# Microcontroller.net
KiCad netlist of a schematic drawn in Altium Designer
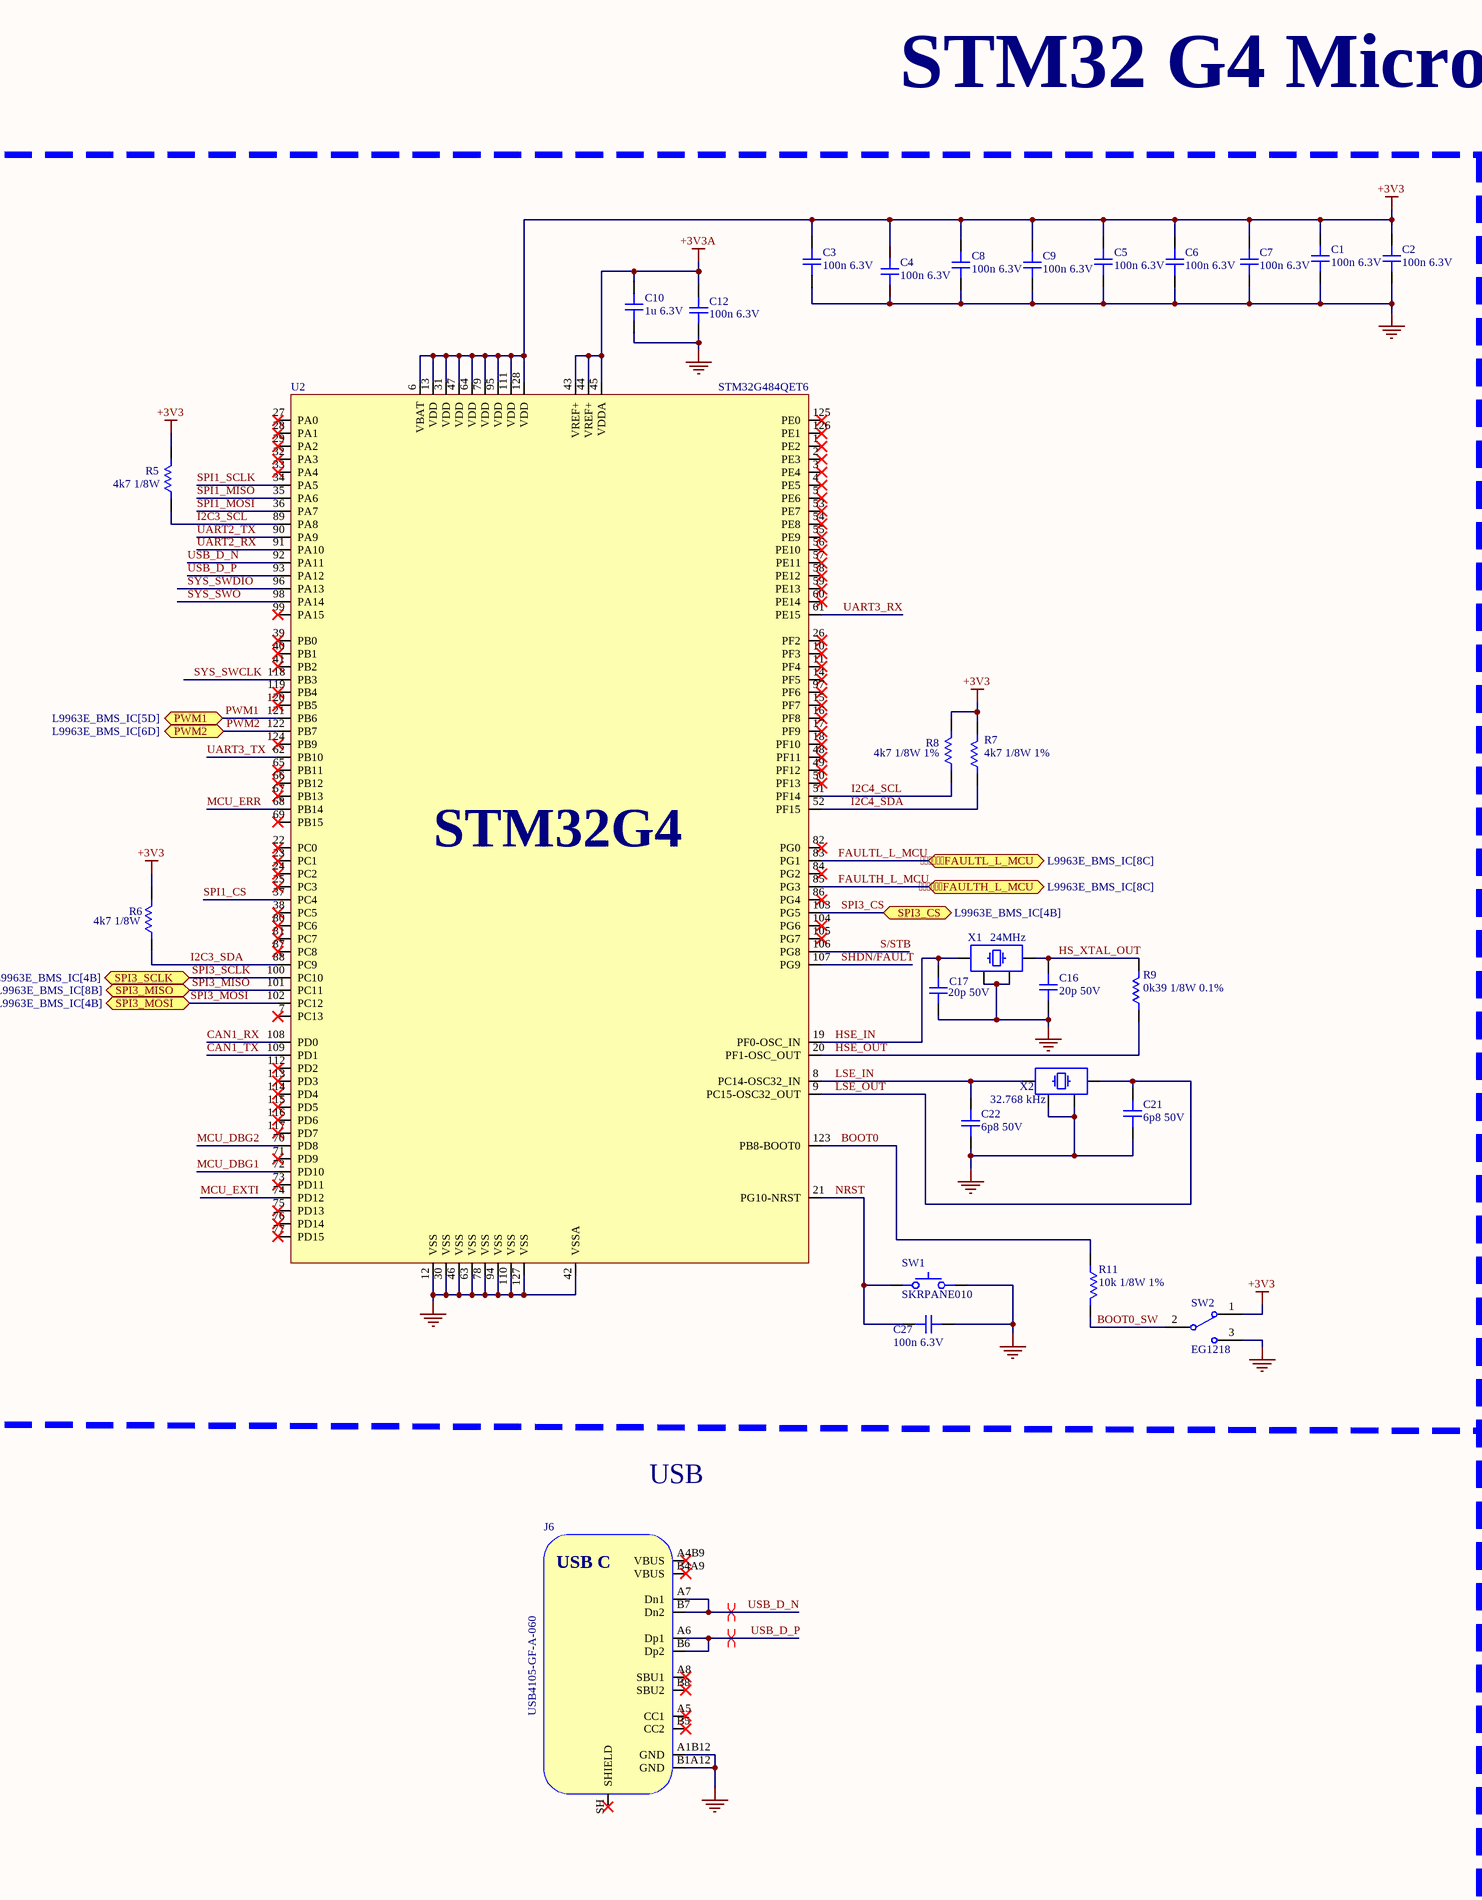
[diagram p0: Microcontroller.SchDoc, left]
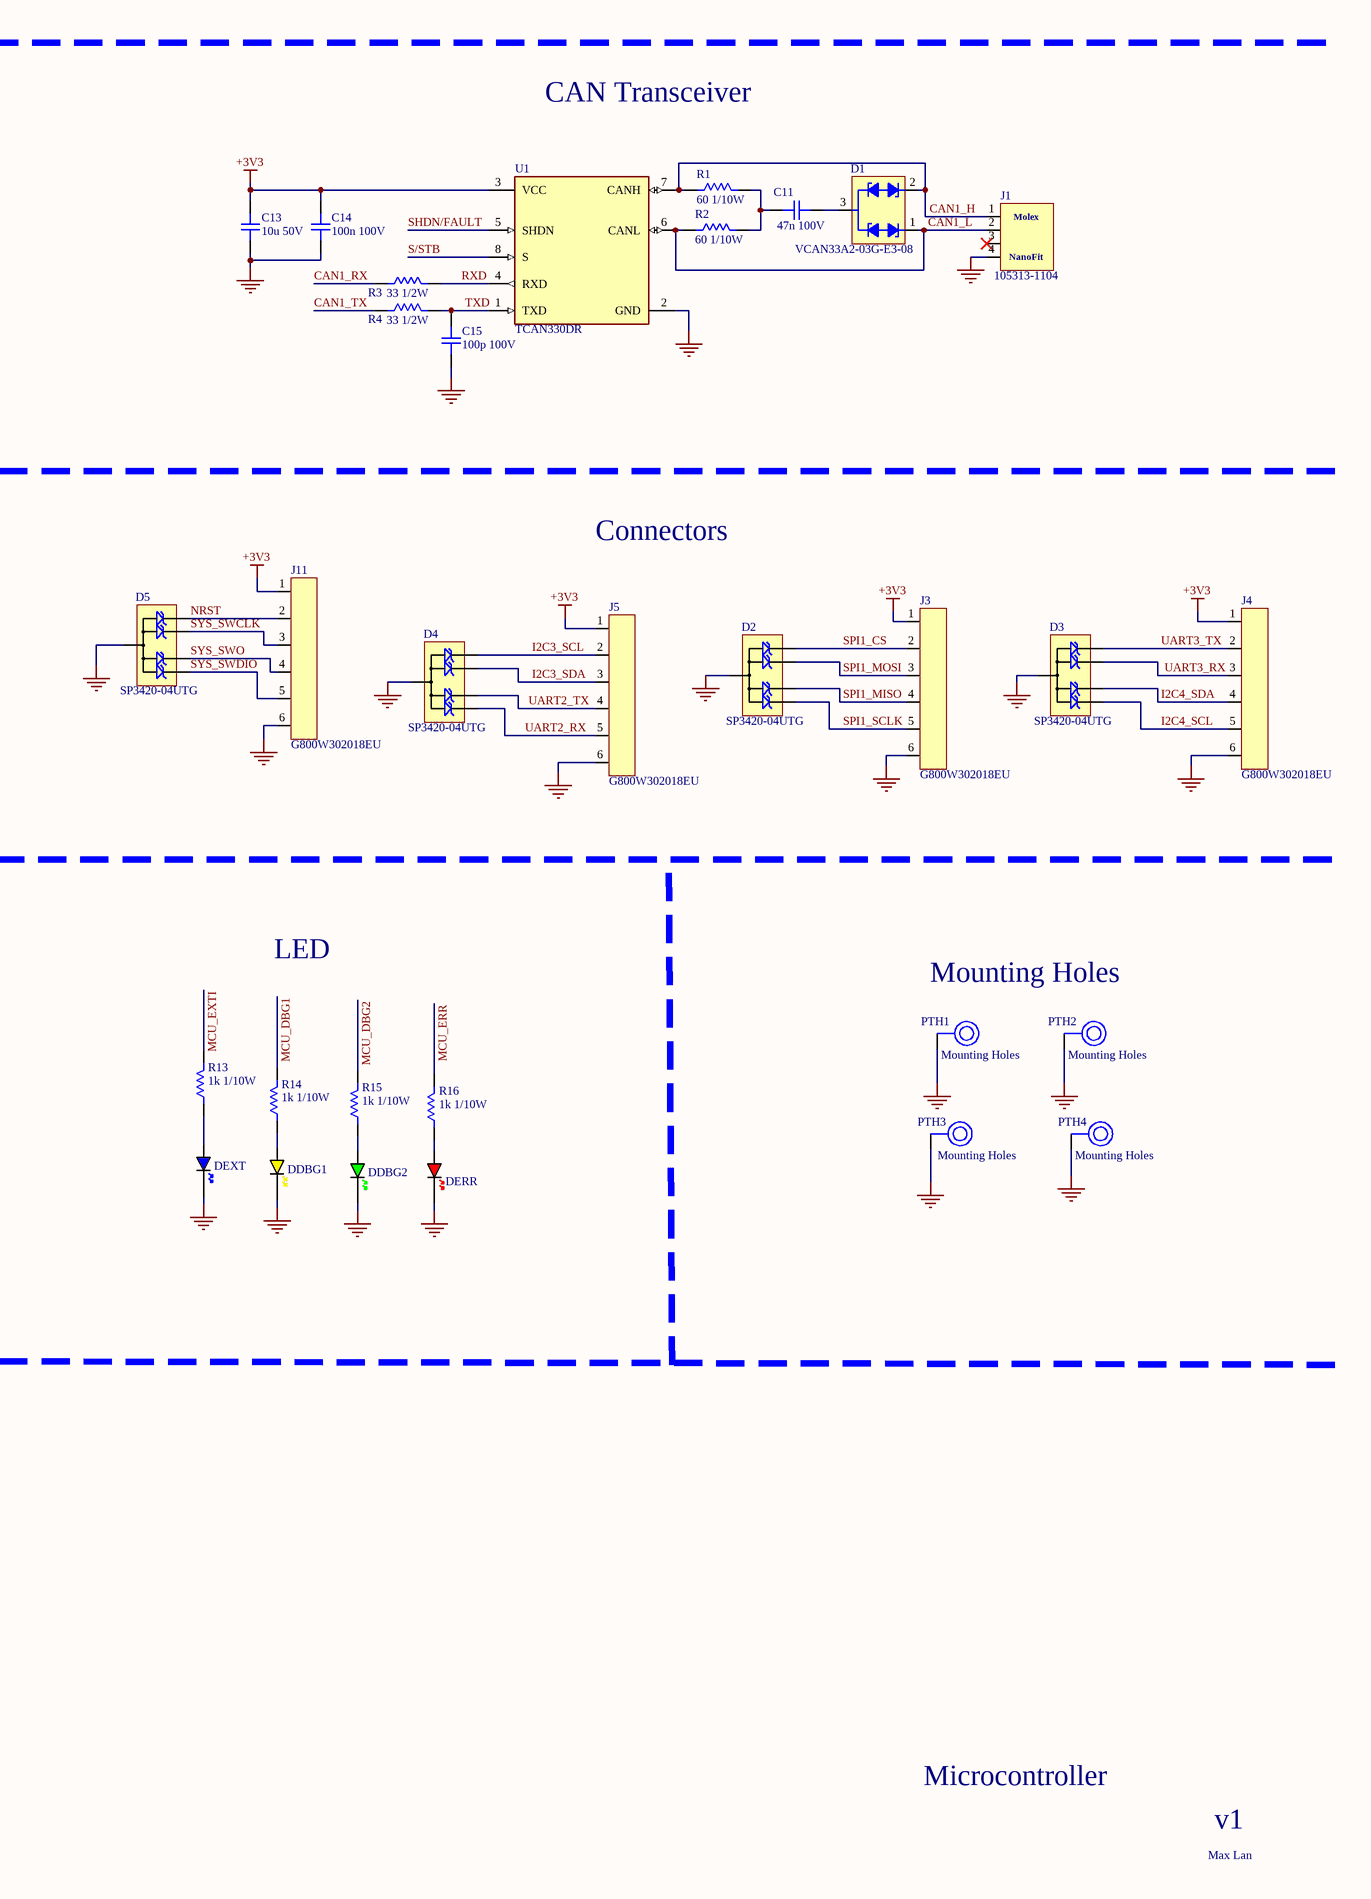
[diagram p1: Microcontroller.SchDoc, right]

(export (version "E")
  (design (tool "Eeschema 10.0.6"))
  (components
    (comp (ref "C1")
      (value "100n 6.3V")
      (footprint "CAP_0603")
      (description "Multilayer Ceramic Capacitors MLCC - SMD/SMT 6.3V .1uF X7R 0603 10%")
      (fields
        (field (name "MANUFACTURER") "KYOCERA AVX")
        (field (name "MANUFACTURER PART NUMBER") "KGM15AR70J104KT")
      )
      (libsource (lib "Schematic-Lib-PhilsLab") (part "KGM15AR70J104KT"))
    )
    (comp (ref "C2")
      (value "100n 6.3V")
      (footprint "CAP_0603")
      (description "Multilayer Ceramic Capacitors MLCC - SMD/SMT 6.3V .1uF X7R 0603 10%")
      (fields
        (field (name "MANUFACTURER") "KYOCERA AVX")
        (field (name "MANUFACTURER PART NUMBER") "KGM15AR70J104KT")
      )
      (libsource (lib "Schematic-Lib-PhilsLab") (part "KGM15AR70J104KT"))
    )
    (comp (ref "C3")
      (value "100n 6.3V")
      (footprint "CAP_0603")
      (description "Multilayer Ceramic Capacitors MLCC - SMD/SMT 6.3V .1uF X7R 0603 10%")
      (fields
        (field (name "MANUFACTURER") "KYOCERA AVX")
        (field (name "MANUFACTURER PART NUMBER") "KGM15AR70J104KT")
      )
      (libsource (lib "Schematic-Lib-PhilsLab") (part "KGM15AR70J104KT"))
    )
    (comp (ref "C4")
      (value "100n 6.3V")
      (footprint "CAP_0603")
      (description "Multilayer Ceramic Capacitors MLCC - SMD/SMT 6.3V .1uF X7R 0603 10%")
      (fields
        (field (name "MANUFACTURER") "KYOCERA AVX")
        (field (name "MANUFACTURER PART NUMBER") "KGM15AR70J104KT")
      )
      (libsource (lib "Schematic-Lib-PhilsLab") (part "KGM15AR70J104KT"))
    )
    (comp (ref "C5")
      (value "100n 6.3V")
      (footprint "CAP_0603")
      (description "Multilayer Ceramic Capacitors MLCC - SMD/SMT 6.3V .1uF X7R 0603 10%")
      (fields
        (field (name "MANUFACTURER") "KYOCERA AVX")
        (field (name "MANUFACTURER PART NUMBER") "KGM15AR70J104KT")
      )
      (libsource (lib "Schematic-Lib-PhilsLab") (part "KGM15AR70J104KT"))
    )
    (comp (ref "C6")
      (value "100n 6.3V")
      (footprint "CAP_0603")
      (description "Multilayer Ceramic Capacitors MLCC - SMD/SMT 6.3V .1uF X7R 0603 10%")
      (fields
        (field (name "MANUFACTURER") "KYOCERA AVX")
        (field (name "MANUFACTURER PART NUMBER") "KGM15AR70J104KT")
      )
      (libsource (lib "Schematic-Lib-PhilsLab") (part "KGM15AR70J104KT"))
    )
    (comp (ref "C7")
      (value "100n 6.3V")
      (footprint "CAP_0603")
      (description "Multilayer Ceramic Capacitors MLCC - SMD/SMT 6.3V .1uF X7R 0603 10%")
      (fields
        (field (name "MANUFACTURER") "KYOCERA AVX")
        (field (name "MANUFACTURER PART NUMBER") "KGM15AR70J104KT")
      )
      (libsource (lib "Schematic-Lib-PhilsLab") (part "KGM15AR70J104KT"))
    )
    (comp (ref "C8")
      (value "100n 6.3V")
      (footprint "CAP_0603")
      (description "Multilayer Ceramic Capacitors MLCC - SMD/SMT 6.3V .1uF X7R 0603 10%")
      (fields
        (field (name "MANUFACTURER") "KYOCERA AVX")
        (field (name "MANUFACTURER PART NUMBER") "KGM15AR70J104KT")
      )
      (libsource (lib "Schematic-Lib-PhilsLab") (part "KGM15AR70J104KT"))
    )
    (comp (ref "C9")
      (value "100n 6.3V")
      (footprint "CAP_0603")
      (description "Multilayer Ceramic Capacitors MLCC - SMD/SMT 6.3V .1uF X7R 0603 10%")
      (fields
        (field (name "MANUFACTURER") "KYOCERA AVX")
        (field (name "MANUFACTURER PART NUMBER") "KGM15AR70J104KT")
      )
      (libsource (lib "Schematic-Lib-PhilsLab") (part "KGM15AR70J104KT"))
    )
    (comp (ref "C10")
      (value "1u 6.3V")
      (footprint "CAP_0603")
      (description "Multilayer Ceramic Capacitors MLCC - SMD/SMT 6.3 Vo 1 uF 0603 X7R 10 % AECQ200")
      (fields
        (field (name "MANUFACTURER") "KEMET")
        (field (name "MANUFACTURER PART NUMBER") "C0603X105K9RACAUTO")
      )
      (libsource (lib "Schematic-Lib-PhilsLab") (part "C0603X105K9RACAUTO"))
    )
    (comp (ref "C11")
      (value "47n 100V")
      (footprint "CAP_0603")
      (description "Multilayer Ceramic Capacitors MLCC - SMD/SMT 100V 0.047uF X7R 0603 5%")
      (fields
        (field (name "MANUFACTURER") "KEMET")
        (field (name "MANUFACTURER PART NUMBER") "C0603C473J1RACTU")
      )
      (libsource (lib "Schematic-Lib-PhilsLab") (part "C0603C473J1RACTU"))
    )
    (comp (ref "C12")
      (value "100n 6.3V")
      (footprint "CAP_0603")
      (description "Multilayer Ceramic Capacitors MLCC - SMD/SMT 6.3V .1uF X7R 0603 10%")
      (fields
        (field (name "MANUFACTURER") "KYOCERA AVX")
        (field (name "MANUFACTURER PART NUMBER") "KGM15AR70J104KT")
      )
      (libsource (lib "Schematic-Lib-PhilsLab") (part "KGM15AR70J104KT"))
    )
    (comp (ref "C13")
      (value "10u 50V")
      (footprint "CAP_1210")
      (description "Multilayer Ceramic Capacitors MLCC - SMD/SMT 50V 10uF X7R 1210 10 % AEC-Q200 FLEXITERM")
      (fields
        (field (name "MANUFACTURER") "KYOCERA AVX")
        (field (name "MANUFACTURER PART NUMBER") "KAF32LR71H106KL")
      )
      (libsource (lib "Schematic-Lib-PhilsLab") (part "KAF32LR71H106KL"))
    )
    (comp (ref "C14")
      (value "100n 100V")
      (footprint "CAP_0603")
      (description "Multilayer Ceramic Capacitors MLCC - SMD/SMT 100V 0.1uF 0603 X7R 10% AECQ2")
      (fields
        (field (name "MANUFACTURER") "TAIYO YUDEN")
        (field (name "MANUFACTURER PART NUMBER") "MAJCH168BB7104KTEA01")
      )
      (libsource (lib "Schematic-Lib-PhilsLab") (part "MAJCH168BB7104KTEA01"))
    )
    (comp (ref "C15")
      (value "100p 100V")
      (footprint "CAP_0603")
      (description "Multilayer Ceramic Capacitors MLCC - SMD/SMT 100V 100pF X7R 0603 5%")
      (fields
        (field (name "MANUFACTURER") "KYOCERA AVX")
        (field (name "MANUFACTURER PART NUMBER") "KGM15AR72A101JT")
      )
      (libsource (lib "Schematic-Lib-PhilsLab") (part "KGM15AR72A101JT"))
    )
    (comp (ref "C16")
      (value "20p 50V")
      (footprint "CAP_0603")
      (description "Multilayer Ceramic Capacitors MLCC - SMD/SMT 50V 20pF 5% X7R 0603")
      (fields (field (name "MANUFACTURER") "KEMET"))
      (libsource (lib "Schematic-Lib-PhilsLab") (part "C0603C200J5RACTU"))
    )
    (comp (ref "C17")
      (value "20p 50V")
      (footprint "CAP_0603")
      (description "Multilayer Ceramic Capacitors MLCC - SMD/SMT 50V 20pF 5% X7R 0603")
      (fields (field (name "MANUFACTURER") "KEMET"))
      (libsource (lib "Schematic-Lib-PhilsLab") (part "C0603C200J5RACTU"))
    )
    (comp (ref "C21")
      (value "6p8 50V")
      (footprint "CAP_0603")
      (description "Multilayer Ceramic Capacitors MLCC - SMD/SMT T101 COMMERCIAL")
      (fields
        (field (name "MANUFACTURER") "KYOCERA AVX")
        (field (name "MANUFACTURER PART NUMBER") "06035C6R8KAT2A")
      )
      (libsource (lib "Schematic-Lib-PhilsLab") (part "06035C6R8KAT2A"))
    )
    (comp (ref "C22")
      (value "6p8 50V")
      (footprint "CAP_0603")
      (description "Multilayer Ceramic Capacitors MLCC - SMD/SMT T101 COMMERCIAL")
      (fields
        (field (name "MANUFACTURER") "KYOCERA AVX")
        (field (name "MANUFACTURER PART NUMBER") "06035C6R8KAT2A")
      )
      (libsource (lib "Schematic-Lib-PhilsLab") (part "06035C6R8KAT2A"))
    )
    (comp (ref "C27")
      (value "100n 6.3V")
      (footprint "CAP_0603")
      (description "Multilayer Ceramic Capacitors MLCC - SMD/SMT 6.3V .1uF X7R 0603 10%")
      (fields
        (field (name "MANUFACTURER") "KYOCERA AVX")
        (field (name "MANUFACTURER PART NUMBER") "KGM15AR70J104KT")
      )
      (libsource (lib "Schematic-Lib-PhilsLab") (part "KGM15AR70J104KT"))
    )
    (comp (ref "D1")
      (value "VCAN33A2-03G-E3-08")
      (footprint "VCAN33A2-03G-E3-08")
      (description "ESD Protection Diodes / TVS Diodes 9.5pF 33V SOT-323")
      (libsource (lib "Schematic-Lib-PhilsLab") (part "VCAN33A2-03G-E3-08"))
    )
    (comp (ref "D2")
      (value "SP3420-04UTG")
      (footprint "uDFN-10")
      (description "TVS Diode Array Low Capacitance ESD Protection 4-Channel (Vwork=3V3, Vclamp=6V)")
      (fields (field (name "MANUFACTURER") "Littelfuse"))
      (libsource (lib "Schematic-Lib-PhilsLab") (part "SP3420-04UTG"))
    )
    (comp (ref "D3")
      (value "SP3420-04UTG")
      (footprint "uDFN-10")
      (description "TVS Diode Array Low Capacitance ESD Protection 4-Channel (Vwork=3V3, Vclamp=6V)")
      (fields (field (name "MANUFACTURER") "Littelfuse"))
      (libsource (lib "Schematic-Lib-PhilsLab") (part "SP3420-04UTG"))
    )
    (comp (ref "D4")
      (value "SP3420-04UTG")
      (footprint "uDFN-10")
      (description "TVS Diode Array Low Capacitance ESD Protection 4-Channel (Vwork=3V3, Vclamp=6V)")
      (fields (field (name "MANUFACTURER") "Littelfuse"))
      (libsource (lib "Schematic-Lib-PhilsLab") (part "SP3420-04UTG"))
    )
    (comp (ref "D5")
      (value "SP3420-04UTG")
      (footprint "uDFN-10")
      (description "TVS Diode Array Low Capacitance ESD Protection 4-Channel (Vwork=3V3, Vclamp=6V)")
      (fields (field (name "MANUFACTURER") "Littelfuse"))
      (libsource (lib "Schematic-Lib-PhilsLab") (part "SP3420-04UTG"))
    )
    (comp (ref "DDBG1")
      (value "YELLOW")
      (footprint "LED_0603_YELLOW")
      (description "LED 0603 YELLOW SMD")
      (libsource (lib "Schematic-Lib-PhilsLab") (part "LED_0603_YELLOW"))
    )
    (comp (ref "DDBG2")
      (value "GREEN")
      (footprint "LED_0603_GREEN")
      (description "LED 0603 GREEN SMD")
      (libsource (lib "Schematic-Lib-PhilsLab") (part "LED_0603_GREEN"))
    )
    (comp (ref "DERR")
      (value "RED")
      (footprint "LED_0603_RED")
      (description "LED 0603 RED SMD")
      (libsource (lib "Schematic-Lib-PhilsLab") (part "LED_0603_RED"))
    )
    (comp (ref "DEXT")
      (value "BLUE")
      (footprint "LED_0603_BLUE")
      (description "LED 0603 BLUE SMD")
      (libsource (lib "Schematic-Lib-PhilsLab") (part "LED_0603_BLUE"))
    )
    (comp (ref "J1")
      (value "105313-1104")
      (footprint "105313-1104")
      (fields (field (name "MANUFACTURER") "Molex"))
      (libsource (lib "Schematic-Lib-PhilsLab") (part "105313-1104"))
    )
    (comp (ref "J3")
      (value "G800W302018EU")
      (footprint "G800W302018EU")
      (description "Pin Header 6 Position 2.54mm Pitch")
      (fields (field (name "MANUFACTURER") "Amphenol"))
      (libsource (lib "Schematic-Lib-PhilsLab") (part "G800W302018EU"))
    )
    (comp (ref "J4")
      (value "G800W302018EU")
      (footprint "G800W302018EU")
      (description "Pin Header 6 Position 2.54mm Pitch")
      (fields (field (name "MANUFACTURER") "Amphenol"))
      (libsource (lib "Schematic-Lib-PhilsLab") (part "G800W302018EU"))
    )
    (comp (ref "J5")
      (value "G800W302018EU")
      (footprint "G800W302018EU")
      (description "Pin Header 6 Position 2.54mm Pitch")
      (fields (field (name "MANUFACTURER") "Amphenol"))
      (libsource (lib "Schematic-Lib-PhilsLab") (part "G800W302018EU"))
    )
    (comp (ref "J6")
      (value "USB4105-GF-A-060")
      (footprint "USB4105-GF-A-060")
      (description "USB Connector Type C SMT 12 Pin")
      (fields (field (name "MANUFACTURER") "GCT"))
      (libsource (lib "Schematic-Lib-PhilsLab") (part "USB4105-GF-A-060"))
    )
    (comp (ref "J11")
      (value "G800W302018EU")
      (footprint "G800W302018EU")
      (description "Pin Header 6 Position 2.54mm Pitch")
      (fields (field (name "MANUFACTURER") "Amphenol"))
      (libsource (lib "Schematic-Lib-PhilsLab") (part "G800W302018EU"))
    )
    (comp (ref "PTH1")
      (value "Mounting Holes")
      (footprint "Mounting Hole")
      (libsource (lib "Schematic-Lib-PhilsLab") (part "Mounting Holes"))
    )
    (comp (ref "PTH2")
      (value "Mounting Holes")
      (footprint "Mounting Hole")
      (libsource (lib "Schematic-Lib-PhilsLab") (part "Mounting Holes"))
    )
    (comp (ref "PTH3")
      (value "Mounting Holes")
      (footprint "Mounting Hole")
      (libsource (lib "Schematic-Lib-PhilsLab") (part "Mounting Holes"))
    )
    (comp (ref "PTH4")
      (value "Mounting Holes")
      (footprint "Mounting Hole")
      (libsource (lib "Schematic-Lib-PhilsLab") (part "Mounting Holes"))
    )
    (comp (ref "R1")
      (value "60 1/10W")
      (footprint "RES_0201")
      (description "Thick Film Resistors - SMD")
      (fields
        (field (name "MANUFACTURER") "KOA Speer")
        (field (name "MANUFACTURER PART NUMBER") "RK73H1HRTTCM60R4F")
      )
      (libsource (lib "Schematic-Lib-PhilsLab") (part "RK73H1HRTTCM60R4F"))
    )
    (comp (ref "R2")
      (value "60 1/10W")
      (footprint "RES_0201")
      (description "Thick Film Resistors - SMD")
      (fields
        (field (name "MANUFACTURER") "KOA Speer")
        (field (name "MANUFACTURER PART NUMBER") "RK73H1HRTTCM60R4F")
      )
      (libsource (lib "Schematic-Lib-PhilsLab") (part "RK73H1HRTTCM60R4F"))
    )
    (comp (ref "R3")
      (value "33 1/2W")
      (footprint "RES_1206")
      (description "Thick Film Resistors - SMD 33 Ohms 1/2 W 1206 1 % AEC-Q200")
      (fields
        (field (name "MANUFACTURER") "YAGEO")
        (field (name "MANUFACTURER PART NUMBER") "SR1206FR-7W33RL")
      )
      (libsource (lib "Schematic-Lib-PhilsLab") (part "SR1206FR-7W33RL"))
    )
    (comp (ref "R4")
      (value "33 1/2W")
      (footprint "RES_1206")
      (description "Thick Film Resistors - SMD 33 Ohms 1/2 W 1206 1 % AEC-Q200")
      (fields
        (field (name "MANUFACTURER") "YAGEO")
        (field (name "MANUFACTURER PART NUMBER") "SR1206FR-7W33RL")
      )
      (libsource (lib "Schematic-Lib-PhilsLab") (part "SR1206FR-7W33RL"))
    )
    (comp (ref "R5")
      (value "4k7 1/8W")
      (footprint "RES_0603")
      (description "Thick Film Resistors - SMD 1/8 Watt 4.7Kohms 1%")
      (fields
        (field (name "MANUFACTURER") "Vishay")
        (field (name "MANUFACTURER PART NUMBER") "CRCW06034K70FKEA")
      )
      (libsource (lib "Schematic-Lib-PhilsLab") (part "CRCW06034K70FKEA"))
    )
    (comp (ref "R6")
      (value "4k7 1/8W")
      (footprint "RES_0603")
      (description "Thick Film Resistors - SMD 1/8 Watt 4.7Kohms 1%")
      (fields
        (field (name "MANUFACTURER") "Vishay")
        (field (name "MANUFACTURER PART NUMBER") "CRCW06034K70FKEA")
      )
      (libsource (lib "Schematic-Lib-PhilsLab") (part "CRCW06034K70FKEA"))
    )
    (comp (ref "R7")
      (value "4k7 1/8W 1%")
      (footprint "RES_0603")
      (description "Thick Film Resistors - SMD 1/8 Watt 4.7Kohms 1%")
      (fields
        (field (name "MANUFACTURER") "Vishay")
        (field (name "MANUFACTURER PART NUMBER") "CRCW06034K70FKEA")
      )
      (libsource (lib "Schematic-Lib-PhilsLab") (part "CRCW06034K70FKEA"))
    )
    (comp (ref "R8")
      (value "4k7 1/8W 1%")
      (footprint "RES_0603")
      (description "Thick Film Resistors - SMD 1/8 Watt 4.7Kohms 1%")
      (fields
        (field (name "MANUFACTURER") "Vishay")
        (field (name "MANUFACTURER PART NUMBER") "CRCW06034K70FKEA")
      )
      (libsource (lib "Schematic-Lib-PhilsLab") (part "CRCW06034K70FKEA"))
    )
    (comp (ref "R9")
      (value "0k39 1/8W 0.1%")
      (footprint "RES_0603")
      (description "Thin Film Resistors - SMD 0603 0.1% 390ohm 25ppm SMD")
      (fields
        (field (name "MANUFACTURER") "Panasonic")
        (field (name "MANUFACTURER PART NUMBER") "ERA-3VEB3900V")
      )
      (libsource (lib "Schematic-Lib-PhilsLab") (part "ERA-3VEB3900V"))
    )
    (comp (ref "R11")
      (value "10k 1/8W 1%")
      (footprint "RES_0603")
      (description "Thick Film Resistors - SMD 10K OHM 1%")
      (fields
        (field (name "MANUFACTURER") "Vishay")
        (field (name "MANUFACTURER PART NUMBER") "CRCW060310K0FKEI")
      )
      (libsource (lib "Schematic-Lib-PhilsLab") (part "CRCW060310K0FKEI"))
    )
    (comp (ref "R13")
      (value "1k 1/10W")
      (footprint "RES_0603")
      (description "Thick Film Resistors - SMD Res 0603 1k 1% 100mW TC100 low lead")
      (fields
        (field (name "MANUFACTURER") "Bourns")
        (field (name "MANUFACTURER PART NUMBER") "CR0603-FX-1001EPF")
      )
      (libsource (lib "Schematic-Lib-PhilsLab") (part "CR0603-FX-1001EPF"))
    )
    (comp (ref "R14")
      (value "1k 1/10W")
      (footprint "RES_0603")
      (description "Thick Film Resistors - SMD Res 0603 1k 1% 100mW TC100 low lead")
      (fields
        (field (name "MANUFACTURER") "Bourns")
        (field (name "MANUFACTURER PART NUMBER") "CR0603-FX-1001EPF")
      )
      (libsource (lib "Schematic-Lib-PhilsLab") (part "CR0603-FX-1001EPF"))
    )
    (comp (ref "R15")
      (value "1k 1/10W")
      (footprint "RES_0603")
      (description "Thick Film Resistors - SMD Res 0603 1k 1% 100mW TC100 low lead")
      (fields
        (field (name "MANUFACTURER") "Bourns")
        (field (name "MANUFACTURER PART NUMBER") "CR0603-FX-1001EPF")
      )
      (libsource (lib "Schematic-Lib-PhilsLab") (part "CR0603-FX-1001EPF"))
    )
    (comp (ref "R16")
      (value "1k 1/10W")
      (footprint "RES_0603")
      (description "Thick Film Resistors - SMD Res 0603 1k 1% 100mW TC100 low lead")
      (fields
        (field (name "MANUFACTURER") "Bourns")
        (field (name "MANUFACTURER PART NUMBER") "CR0603-FX-1001EPF")
      )
      (libsource (lib "Schematic-Lib-PhilsLab") (part "CR0603-FX-1001EPF"))
    )
    (comp (ref "SW1")
      (value "SKRPANE010")
      (footprint "SKRPANE010")
      (description "Tactile Switch SMD SPST")
      (fields (field (name "MANUFACTURER") "Alps Alpine"))
      (libsource (lib "Schematic-Lib-PhilsLab") (part "SKRPANE010"))
    )
    (comp (ref "SW2")
      (value "EG1218")
      (footprint "ESWI-EG1218_V")
      (description "Slide Switch, 500 V, -20 to 70 degC, 3-Pin THD, RoHS")
      (libsource (lib "Altium Content Vault") (part "SW-SPDT-3_B"))
    )
    (comp (ref "U1")
      (value "TCAN330DR")
      (footprint "FP-D0008A-IPC_A")
      (description "IC TRANSCEIVER 1/1 8SOIC")
      (libsource (lib "Altium Content Vault") (part "2cff83dcd93ccda1ab41292df9c405d"))
    )
    (comp (ref "U2")
      (value "STM32G484QET6")
      (footprint "LQFP-128")
      (description "STM32G4 Microcontroller LQFP-128 170 MHz 107 I/O")
      (fields (field (name "MANUFACTURER") "STMicroelectronics"))
      (libsource (lib "Schematic-Lib-PhilsLab") (part "STM32G484QET6"))
    )
    (comp (ref "X1")
      (value "24MHz")
      (footprint "XTAL_3225")
      (description "Crystal SMD 24MHz 10PPM 7pF 3225")
      (fields
        (field (name "MANUFACTURER") "Epson")
        (field (name "MANUFACTURER PART NUMBER") "TSX-3225 24.0000MF15X-AC")
      )
      (libsource (lib "Schematic-Lib-PhilsLab") (part "TSX-3225_24.0000MF15X-AC"))
    )
    (comp (ref "X2")
      (value "32.768 kHz")
      (footprint "G43270009")
      (description "Crystals Crystal Plastic SMD8038 T&R 3K.\r\n32.768 kHz")
      (fields (field (name "TOLERANCE") "10 PPM"))
      (libsource (lib "Schematic-Lib-PhilsLab") (part "G43270009"))
    )
  )
  (nets
    (net (code "1") (name "+3V3") (class "Default")
      (node (ref "C1") (pin "2") (pinfunction "2_2") (pintype "passive"))
      (node (ref "C13") (pin "2") (pinfunction "2_2") (pintype "passive"))
      (node (ref "C14") (pin "2") (pinfunction "2_2") (pintype "passive"))
      (node (ref "C2") (pin "2") (pinfunction "2_2") (pintype "passive"))
      (node (ref "C3") (pin "2") (pinfunction "2_2") (pintype "passive"))
      (node (ref "C4") (pin "2") (pinfunction "2_2") (pintype "passive"))
      (node (ref "C5") (pin "2") (pinfunction "2_2") (pintype "passive"))
      (node (ref "C6") (pin "2") (pinfunction "2_2") (pintype "passive"))
      (node (ref "C7") (pin "2") (pinfunction "2_2") (pintype "passive"))
      (node (ref "C8") (pin "2") (pinfunction "2_2") (pintype "passive"))
      (node (ref "C9") (pin "2") (pinfunction "2_2") (pintype "passive"))
      (node (ref "J11") (pin "1") (pinfunction "1_1") (pintype "passive"))
      (node (ref "J3") (pin "1") (pinfunction "1_1") (pintype "passive"))
      (node (ref "J4") (pin "1") (pinfunction "1_1") (pintype "passive"))
      (node (ref "J5") (pin "1") (pinfunction "1_1") (pintype "passive"))
      (node (ref "R5") (pin "2") (pinfunction "2_2") (pintype "passive"))
      (node (ref "R6") (pin "2") (pinfunction "2_2") (pintype "passive"))
      (node (ref "R7") (pin "2") (pinfunction "2_2") (pintype "passive"))
      (node (ref "R8") (pin "2") (pinfunction "2_2") (pintype "passive"))
      (node (ref "SW2") (pin "1") (pinfunction "1_1") (pintype "passive"))
      (node (ref "U1") (pin "3") (pinfunction "VCC_3") (pintype "power_in"))
      (node (ref "U2") (pin "111") (pinfunction "VDD_111") (pintype "passive"))
      (node (ref "U2") (pin "128") (pinfunction "VDD_128") (pintype "passive"))
      (node (ref "U2") (pin "13") (pinfunction "VDD_13") (pintype "passive"))
      (node (ref "U2") (pin "31") (pinfunction "VDD_31") (pintype "passive"))
      (node (ref "U2") (pin "47") (pinfunction "VDD_47") (pintype "passive"))
      (node (ref "U2") (pin "6") (pinfunction "VBAT_6") (pintype "passive"))
      (node (ref "U2") (pin "64") (pinfunction "VDD_64") (pintype "passive"))
      (node (ref "U2") (pin "79") (pinfunction "VDD_79") (pintype "passive"))
      (node (ref "U2") (pin "95") (pinfunction "VDD_95") (pintype "passive"))
    )
    (net (code "2") (name "+3V3A") (class "Default")
      (node (ref "C10") (pin "2") (pinfunction "2_2") (pintype "passive"))
      (node (ref "C12") (pin "2") (pinfunction "2_2") (pintype "passive"))
      (node (ref "U2") (pin "43") (pinfunction "VREF+_43") (pintype "passive"))
      (node (ref "U2") (pin "44") (pinfunction "VREF+_44") (pintype "passive"))
      (node (ref "U2") (pin "45") (pinfunction "VDDA_45") (pintype "passive"))
    )
    (net (code "3") (name "/BOOT0") (class "Default")
      (node (ref "R11") (pin "1") (pinfunction "1_1") (pintype "passive"))
      (node (ref "U2") (pin "123") (pinfunction "PB8-BOOT0_123") (pintype "passive"))
    )
    (net (code "4") (name "/BOOT0_SW") (class "Default")
      (node (ref "R11") (pin "2") (pinfunction "2_2") (pintype "passive"))
      (node (ref "SW2") (pin "2") (pinfunction "COM_2") (pintype "passive"))
    )
    (net (code "5") (name "/CAN1_H") (class "Default")
      (node (ref "D1") (pin "2") (pinfunction "2_2") (pintype "passive"))
      (node (ref "J1") (pin "1") (pinfunction "1_1") (pintype "passive"))
      (node (ref "R1") (pin "1") (pinfunction "1_1") (pintype "passive"))
      (node (ref "U1") (pin "7") (pinfunction "CANH_7") (pintype "bidirectional"))
    )
    (net (code "6") (name "/CAN1_L") (class "Default")
      (node (ref "D1") (pin "1") (pinfunction "1_1") (pintype "passive"))
      (node (ref "J1") (pin "2") (pinfunction "2_2") (pintype "passive"))
      (node (ref "R2") (pin "1") (pinfunction "1_1") (pintype "passive"))
      (node (ref "U1") (pin "6") (pinfunction "CANL_6") (pintype "bidirectional"))
    )
    (net (code "7") (name "/CAN1_RX") (class "Default")
      (node (ref "R3") (pin "1") (pinfunction "1_1") (pintype "passive"))
      (node (ref "U2") (pin "108") (pinfunction "PD0_108") (pintype "passive"))
    )
    (net (code "8") (name "/CAN1_TX") (class "Default")
      (node (ref "R4") (pin "1") (pinfunction "1_1") (pintype "passive"))
      (node (ref "U2") (pin "109") (pinfunction "PD1_109") (pintype "passive"))
    )
    (net (code "9") (name "/FAULTH_L_MCU") (class "Default")
      (node (ref "U2") (pin "85") (pinfunction "PG3_85") (pintype "passive"))
    )
    (net (code "10") (name "/FAULTL_L_MCU") (class "Default")
      (node (ref "U2") (pin "83") (pinfunction "PG1_83") (pintype "passive"))
    )
    (net (code "11") (name "/HSE_IN") (class "Default")
      (node (ref "C17") (pin "2") (pinfunction "2_2") (pintype "passive"))
      (node (ref "U2") (pin "19") (pinfunction "PF0-OSC_IN_19") (pintype "passive"))
      (node (ref "X1") (pin "1") (pinfunction "1_1") (pintype "passive"))
    )
    (net (code "12") (name "/HSE_OUT") (class "Default")
      (node (ref "R9") (pin "1") (pinfunction "1_1") (pintype "passive"))
      (node (ref "U2") (pin "20") (pinfunction "PF1-OSC_OUT_20") (pintype "passive"))
    )
    (net (code "13") (name "/HS_XTAL_OUT") (class "Default")
      (node (ref "C16") (pin "2") (pinfunction "2_2") (pintype "passive"))
      (node (ref "R9") (pin "2") (pinfunction "2_2") (pintype "passive"))
      (node (ref "X1") (pin "3") (pinfunction "3_3") (pintype "passive"))
    )
    (net (code "14") (name "/I2C3_SCL") (class "Default")
      (node (ref "D4") (pin "110") (pintype "passive"))
      (node (ref "J5") (pin "2") (pinfunction "2_2") (pintype "passive"))
      (node (ref "R5") (pin "1") (pinfunction "1_1") (pintype "passive"))
      (node (ref "U2") (pin "89") (pinfunction "PA8_89") (pintype "passive"))
    )
    (net (code "15") (name "/I2C3_SDA") (class "Default")
      (node (ref "D4") (pin "29") (pintype "passive"))
      (node (ref "J5") (pin "3") (pinfunction "3_3") (pintype "passive"))
      (node (ref "R6") (pin "1") (pinfunction "1_1") (pintype "passive"))
      (node (ref "U2") (pin "88") (pinfunction "PC9_88") (pintype "passive"))
    )
    (net (code "16") (name "/I2C4_SCL") (class "Default")
      (node (ref "D3") (pin "56") (pintype "passive"))
      (node (ref "J4") (pin "5") (pinfunction "5_5") (pintype "passive"))
      (node (ref "R8") (pin "1") (pinfunction "1_1") (pintype "passive"))
      (node (ref "U2") (pin "51") (pinfunction "PF14_51") (pintype "passive"))
    )
    (net (code "17") (name "/I2C4_SDA") (class "Default")
      (node (ref "D3") (pin "47") (pintype "passive"))
      (node (ref "J4") (pin "4") (pinfunction "4_4") (pintype "passive"))
      (node (ref "R7") (pin "1") (pinfunction "1_1") (pintype "passive"))
      (node (ref "U2") (pin "52") (pinfunction "PF15_52") (pintype "passive"))
    )
    (net (code "18") (name "/LSE_IN") (class "Default")
      (node (ref "C22") (pin "2") (pinfunction "2_2") (pintype "passive"))
      (node (ref "U2") (pin "8") (pinfunction "PC14-OSC32_IN_8") (pintype "passive"))
      (node (ref "X2") (pin "1") (pinfunction "1_1") (pintype "passive"))
    )
    (net (code "19") (name "/LSE_OUT") (class "Default")
      (node (ref "C21") (pin "1") (pinfunction "1_1") (pintype "passive"))
      (node (ref "U2") (pin "9") (pinfunction "PC15-OSC32_OUT_9") (pintype "passive"))
      (node (ref "X2") (pin "3") (pinfunction "3_3") (pintype "passive"))
    )
    (net (code "20") (name "/MCU_DBG1") (class "Default")
      (node (ref "R14") (pin "2") (pinfunction "2_2") (pintype "passive"))
      (node (ref "U2") (pin "72") (pinfunction "PD10_72") (pintype "passive"))
    )
    (net (code "21") (name "/MCU_DBG2") (class "Default")
      (node (ref "R15") (pin "2") (pinfunction "2_2") (pintype "passive"))
      (node (ref "U2") (pin "70") (pinfunction "PD8_70") (pintype "passive"))
    )
    (net (code "22") (name "/MCU_ERR") (class "Default")
      (node (ref "R16") (pin "2") (pinfunction "2_2") (pintype "passive"))
      (node (ref "U2") (pin "68") (pinfunction "PB14_68") (pintype "passive"))
    )
    (net (code "23") (name "/MCU_EXTI") (class "Default")
      (node (ref "R13") (pin "2") (pinfunction "2_2") (pintype "passive"))
      (node (ref "U2") (pin "74") (pinfunction "PD12_74") (pintype "passive"))
    )
    (net (code "24") (name "/NRST") (class "Default")
      (node (ref "C27") (pin "2") (pinfunction "2_2") (pintype "passive"))
      (node (ref "D5") (pin "110") (pintype "passive"))
      (node (ref "J11") (pin "2") (pinfunction "2_2") (pintype "passive"))
      (node (ref "SW1") (pin "12") (pintype "passive"))
      (node (ref "U2") (pin "21") (pinfunction "PG10-NRST_21") (pintype "passive"))
    )
    (net (code "25") (name "/PWM1") (class "Default")
      (node (ref "U2") (pin "121") (pinfunction "PB6_121") (pintype "passive"))
    )
    (net (code "26") (name "/PWM2") (class "Default")
      (node (ref "U2") (pin "122") (pinfunction "PB7_122") (pintype "passive"))
    )
    (net (code "27") (name "/RXD") (class "Default")
      (node (ref "R3") (pin "2") (pinfunction "2_2") (pintype "passive"))
      (node (ref "U1") (pin "4") (pinfunction "RXD_4") (pintype "output"))
    )
    (net (code "28") (name "/SHDN{slash}FAULT") (class "Default")
      (node (ref "U1") (pin "5") (pinfunction "SHDN_5") (pintype "input"))
      (node (ref "U2") (pin "107") (pinfunction "PG9_107") (pintype "passive"))
    )
    (net (code "29") (name "/SPI1_CS") (class "Default")
      (node (ref "D2") (pin "110") (pintype "passive"))
      (node (ref "J3") (pin "2") (pinfunction "2_2") (pintype "passive"))
      (node (ref "U2") (pin "37") (pinfunction "PC4_37") (pintype "passive"))
    )
    (net (code "30") (name "/SPI1_MISO") (class "Default")
      (node (ref "D2") (pin "47") (pintype "passive"))
      (node (ref "J3") (pin "4") (pinfunction "4_4") (pintype "passive"))
      (node (ref "U2") (pin "35") (pinfunction "PA6_35") (pintype "passive"))
    )
    (net (code "31") (name "/SPI1_MOSI") (class "Default")
      (node (ref "D2") (pin "29") (pintype "passive"))
      (node (ref "J3") (pin "3") (pinfunction "3_3") (pintype "passive"))
      (node (ref "U2") (pin "36") (pinfunction "PA7_36") (pintype "passive"))
    )
    (net (code "32") (name "/SPI1_SCLK") (class "Default")
      (node (ref "D2") (pin "56") (pintype "passive"))
      (node (ref "J3") (pin "5") (pinfunction "5_5") (pintype "passive"))
      (node (ref "U2") (pin "34") (pinfunction "PA5_34") (pintype "passive"))
    )
    (net (code "33") (name "/SPI3_CS") (class "Default")
      (node (ref "U2") (pin "103") (pinfunction "PG5_103") (pintype "passive"))
    )
    (net (code "34") (name "/SPI3_MISO") (class "Default")
      (node (ref "U2") (pin "101") (pinfunction "PC11_101") (pintype "passive"))
    )
    (net (code "35") (name "/SPI3_MOSI") (class "Default")
      (node (ref "U2") (pin "102") (pinfunction "PC12_102") (pintype "passive"))
    )
    (net (code "36") (name "/SPI3_SCLK") (class "Default")
      (node (ref "U2") (pin "100") (pinfunction "PC10_100") (pintype "passive"))
    )
    (net (code "37") (name "/SYS_SWCLK") (class "Default")
      (node (ref "D5") (pin "29") (pintype "passive"))
      (node (ref "J11") (pin "3") (pinfunction "3_3") (pintype "passive"))
      (node (ref "U2") (pin "118") (pinfunction "PB3_118") (pintype "passive"))
    )
    (net (code "38") (name "/SYS_SWDIO") (class "Default")
      (node (ref "D5") (pin "56") (pintype "passive"))
      (node (ref "J11") (pin "5") (pinfunction "5_5") (pintype "passive"))
      (node (ref "U2") (pin "96") (pinfunction "PA13_96") (pintype "passive"))
    )
    (net (code "39") (name "/SYS_SWO") (class "Default")
      (node (ref "D5") (pin "47") (pintype "passive"))
      (node (ref "J11") (pin "4") (pinfunction "4_4") (pintype "passive"))
      (node (ref "U2") (pin "98") (pinfunction "PA14_98") (pintype "passive"))
    )
    (net (code "40") (name "/S{slash}STB") (class "Default")
      (node (ref "U1") (pin "8") (pinfunction "S_8") (pintype "input"))
      (node (ref "U2") (pin "106") (pinfunction "PG8_106") (pintype "passive"))
    )
    (net (code "41") (name "/TXD") (class "Default")
      (node (ref "C15") (pin "2") (pinfunction "2_2") (pintype "passive"))
      (node (ref "R4") (pin "2") (pinfunction "2_2") (pintype "passive"))
      (node (ref "U1") (pin "1") (pinfunction "TXD_1") (pintype "input"))
    )
    (net (code "42") (name "/UART2_RX") (class "Default")
      (node (ref "D4") (pin "56") (pintype "passive"))
      (node (ref "J5") (pin "5") (pinfunction "5_5") (pintype "passive"))
      (node (ref "U2") (pin "91") (pinfunction "PA10_91") (pintype "passive"))
    )
    (net (code "43") (name "/UART2_TX") (class "Default")
      (node (ref "D4") (pin "47") (pintype "passive"))
      (node (ref "J5") (pin "4") (pinfunction "4_4") (pintype "passive"))
      (node (ref "U2") (pin "90") (pinfunction "PA9_90") (pintype "passive"))
    )
    (net (code "44") (name "/UART3_RX") (class "Default")
      (node (ref "D3") (pin "29") (pintype "passive"))
      (node (ref "J4") (pin "3") (pinfunction "3_3") (pintype "passive"))
      (node (ref "U2") (pin "61") (pinfunction "PE15_61") (pintype "passive"))
    )
    (net (code "45") (name "/UART3_TX") (class "Default")
      (node (ref "D3") (pin "110") (pintype "passive"))
      (node (ref "J4") (pin "2") (pinfunction "2_2") (pintype "passive"))
      (node (ref "U2") (pin "62") (pinfunction "PB10_62") (pintype "passive"))
    )
    (net (code "46") (name "/USB_D_N") (class "Default")
      (node (ref "J6") (pin "A7") (pinfunction "Dn1_A7") (pintype "passive"))
      (node (ref "J6") (pin "B7") (pinfunction "Dn2_B7") (pintype "passive"))
      (node (ref "U2") (pin "92") (pinfunction "PA11_92") (pintype "passive"))
    )
    (net (code "47") (name "/USB_D_P") (class "Default")
      (node (ref "J6") (pin "A6") (pinfunction "Dp1_A6") (pintype "passive"))
      (node (ref "J6") (pin "B6") (pinfunction "Dp2_B6") (pintype "passive"))
      (node (ref "U2") (pin "93") (pinfunction "PA12_93") (pintype "passive"))
    )
    (net (code "48") (name "GND") (class "Default")
      (node (ref "C1") (pin "1") (pinfunction "1_1") (pintype "passive"))
      (node (ref "C10") (pin "1") (pinfunction "1_1") (pintype "passive"))
      (node (ref "C12") (pin "1") (pinfunction "1_1") (pintype "passive"))
      (node (ref "C13") (pin "1") (pinfunction "1_1") (pintype "passive"))
      (node (ref "C14") (pin "1") (pinfunction "1_1") (pintype "passive"))
      (node (ref "C15") (pin "1") (pinfunction "1_1") (pintype "passive"))
      (node (ref "C16") (pin "1") (pinfunction "1_1") (pintype "passive"))
      (node (ref "C17") (pin "1") (pinfunction "1_1") (pintype "passive"))
      (node (ref "C2") (pin "1") (pinfunction "1_1") (pintype "passive"))
      (node (ref "C21") (pin "2") (pinfunction "2_2") (pintype "passive"))
      (node (ref "C22") (pin "1") (pinfunction "1_1") (pintype "passive"))
      (node (ref "C27") (pin "1") (pinfunction "1_1") (pintype "passive"))
      (node (ref "C3") (pin "1") (pinfunction "1_1") (pintype "passive"))
      (node (ref "C4") (pin "1") (pinfunction "1_1") (pintype "passive"))
      (node (ref "C5") (pin "1") (pinfunction "1_1") (pintype "passive"))
      (node (ref "C6") (pin "1") (pinfunction "1_1") (pintype "passive"))
      (node (ref "C7") (pin "1") (pinfunction "1_1") (pintype "passive"))
      (node (ref "C8") (pin "1") (pinfunction "1_1") (pintype "passive"))
      (node (ref "C9") (pin "1") (pinfunction "1_1") (pintype "passive"))
      (node (ref "D2") (pin "38") (pinfunction "GND_38") (pintype "passive"))
      (node (ref "D3") (pin "38") (pinfunction "GND_38") (pintype "passive"))
      (node (ref "D4") (pin "38") (pinfunction "GND_38") (pintype "passive"))
      (node (ref "D5") (pin "38") (pinfunction "GND_38") (pintype "passive"))
      (node (ref "DDBG1") (pin "K") (pinfunction "K_K") (pintype "passive"))
      (node (ref "DDBG2") (pin "K") (pinfunction "K_K") (pintype "passive"))
      (node (ref "DERR") (pin "K") (pinfunction "K_K") (pintype "passive"))
      (node (ref "DEXT") (pin "K") (pinfunction "K_K") (pintype "passive"))
      (node (ref "J1") (pin "4") (pinfunction "4_4") (pintype "passive"))
      (node (ref "J11") (pin "6") (pinfunction "6_6") (pintype "passive"))
      (node (ref "J3") (pin "6") (pinfunction "6_6") (pintype "passive"))
      (node (ref "J4") (pin "6") (pinfunction "6_6") (pintype "passive"))
      (node (ref "J5") (pin "6") (pinfunction "6_6") (pintype "passive"))
      (node (ref "J6") (pin "A1B12") (pinfunction "GND_A1B12") (pintype "passive"))
      (node (ref "J6") (pin "B1A12") (pinfunction "GND_B1A12") (pintype "passive"))
      (node (ref "PTH1") (pin "1") (pinfunction "1_1") (pintype "passive"))
      (node (ref "PTH2") (pin "1") (pinfunction "1_1") (pintype "passive"))
      (node (ref "PTH3") (pin "1") (pinfunction "1_1") (pintype "passive"))
      (node (ref "PTH4") (pin "1") (pinfunction "1_1") (pintype "passive"))
      (node (ref "SW1") (pin "34") (pintype "passive"))
      (node (ref "SW2") (pin "3") (pinfunction "3_3") (pintype "passive"))
      (node (ref "U1") (pin "2") (pinfunction "GND_2") (pintype "power_in"))
      (node (ref "U2") (pin "110") (pinfunction "VSS_110") (pintype "passive"))
      (node (ref "U2") (pin "12") (pinfunction "VSS_12") (pintype "passive"))
      (node (ref "U2") (pin "127") (pinfunction "VSS_127") (pintype "passive"))
      (node (ref "U2") (pin "30") (pinfunction "VSS_30") (pintype "passive"))
      (node (ref "U2") (pin "42") (pinfunction "VSSA_42") (pintype "passive"))
      (node (ref "U2") (pin "46") (pinfunction "VSS_46") (pintype "passive"))
      (node (ref "U2") (pin "63") (pinfunction "VSS_63") (pintype "passive"))
      (node (ref "U2") (pin "78") (pinfunction "VSS_78") (pintype "passive"))
      (node (ref "U2") (pin "94") (pinfunction "VSS_94") (pintype "passive"))
      (node (ref "X1") (pin "2") (pinfunction "2_2") (pintype "passive"))
      (node (ref "X1") (pin "4") (pinfunction "4_4") (pintype "passive"))
      (node (ref "X2") (pin "2") (pinfunction "2_2") (pintype "passive"))
      (node (ref "X2") (pin "4") (pinfunction "4_4") (pintype "passive"))
    )
    (net (code "49") (name "Net-(C11-Pad1)") (class "Default")
      (node (ref "C11") (pin "1") (pinfunction "1_1") (pintype "passive"))
      (node (ref "R1") (pin "2") (pinfunction "2_2") (pintype "passive"))
      (node (ref "R2") (pin "2") (pinfunction "2_2") (pintype "passive"))
    )
    (net (code "50") (name "Net-(C11-Pad2)") (class "Default")
      (node (ref "C11") (pin "2") (pinfunction "2_2") (pintype "passive"))
      (node (ref "D1") (pin "3") (pinfunction "3_3") (pintype "passive"))
    )
    (net (code "51") (name "Net-(DDBG1-PadA)") (class "Default")
      (node (ref "DDBG1") (pin "A") (pinfunction "A_A") (pintype "passive"))
      (node (ref "R14") (pin "1") (pinfunction "1_1") (pintype "passive"))
    )
    (net (code "52") (name "Net-(DDBG2-PadA)") (class "Default")
      (node (ref "DDBG2") (pin "A") (pinfunction "A_A") (pintype "passive"))
      (node (ref "R15") (pin "1") (pinfunction "1_1") (pintype "passive"))
    )
    (net (code "53") (name "Net-(DERR-PadA)") (class "Default")
      (node (ref "DERR") (pin "A") (pinfunction "A_A") (pintype "passive"))
      (node (ref "R16") (pin "1") (pinfunction "1_1") (pintype "passive"))
    )
    (net (code "54") (name "Net-(DEXT-PadA)") (class "Default")
      (node (ref "DEXT") (pin "A") (pinfunction "A_A") (pintype "passive"))
      (node (ref "R13") (pin "1") (pinfunction "1_1") (pintype "passive"))
    )
    (net (code "55") (name "unconnected-(J1-Pad3)") (class "Default")
      (node (ref "J1") (pin "3") (pinfunction "3_3") (pintype "passive+no_connect"))
    )
    (net (code "56") (name "unconnected-(J6-CC1-PadA5)") (class "Default")
      (node (ref "J6") (pin "A5") (pinfunction "CC1_A5") (pintype "passive+no_connect"))
    )
    (net (code "57") (name "unconnected-(J6-CC2-PadB5)") (class "Default")
      (node (ref "J6") (pin "B5") (pinfunction "CC2_B5") (pintype "passive+no_connect"))
    )
    (net (code "58") (name "unconnected-(J6-SBU1-PadA8)") (class "Default")
      (node (ref "J6") (pin "A8") (pinfunction "SBU1_A8") (pintype "passive+no_connect"))
    )
    (net (code "59") (name "unconnected-(J6-SBU2-PadB8)") (class "Default")
      (node (ref "J6") (pin "B8") (pinfunction "SBU2_B8") (pintype "passive+no_connect"))
    )
    (net (code "60") (name "unconnected-(J6-SHIELD-PadSH)") (class "Default")
      (node (ref "J6") (pin "SH") (pinfunction "SHIELD_SH") (pintype "passive+no_connect"))
    )
    (net (code "61") (name "unconnected-(J6-VBUS-PadA4B9)") (class "Default")
      (node (ref "J6") (pin "A4B9") (pinfunction "VBUS_A4B9") (pintype "passive+no_connect"))
    )
    (net (code "62") (name "unconnected-(J6-VBUS-PadB4A9)") (class "Default")
      (node (ref "J6") (pin "B4A9") (pinfunction "VBUS_B4A9") (pintype "passive+no_connect"))
    )
    (net (code "63") (name "unconnected-(U2-PA0-Pad27)") (class "Default")
      (node (ref "U2") (pin "27") (pinfunction "PA0_27") (pintype "passive+no_connect"))
    )
    (net (code "64") (name "unconnected-(U2-PA1-Pad28)") (class "Default")
      (node (ref "U2") (pin "28") (pinfunction "PA1_28") (pintype "passive+no_connect"))
    )
    (net (code "65") (name "unconnected-(U2-PA2-Pad29)") (class "Default")
      (node (ref "U2") (pin "29") (pinfunction "PA2_29") (pintype "passive+no_connect"))
    )
    (net (code "66") (name "unconnected-(U2-PA3-Pad32)") (class "Default")
      (node (ref "U2") (pin "32") (pinfunction "PA3_32") (pintype "passive+no_connect"))
    )
    (net (code "67") (name "unconnected-(U2-PA4-Pad33)") (class "Default")
      (node (ref "U2") (pin "33") (pinfunction "PA4_33") (pintype "passive+no_connect"))
    )
    (net (code "68") (name "unconnected-(U2-PA15-Pad99)") (class "Default")
      (node (ref "U2") (pin "99") (pinfunction "PA15_99") (pintype "passive+no_connect"))
    )
    (net (code "69") (name "unconnected-(U2-PB0-Pad39)") (class "Default")
      (node (ref "U2") (pin "39") (pinfunction "PB0_39") (pintype "passive+no_connect"))
    )
    (net (code "70") (name "unconnected-(U2-PB1-Pad40)") (class "Default")
      (node (ref "U2") (pin "40") (pinfunction "PB1_40") (pintype "passive+no_connect"))
    )
    (net (code "71") (name "unconnected-(U2-PB2-Pad41)") (class "Default")
      (node (ref "U2") (pin "41") (pinfunction "PB2_41") (pintype "passive+no_connect"))
    )
    (net (code "72") (name "unconnected-(U2-PB4-Pad119)") (class "Default")
      (node (ref "U2") (pin "119") (pinfunction "PB4_119") (pintype "passive+no_connect"))
    )
    (net (code "73") (name "unconnected-(U2-PB5-Pad120)") (class "Default")
      (node (ref "U2") (pin "120") (pinfunction "PB5_120") (pintype "passive+no_connect"))
    )
    (net (code "74") (name "unconnected-(U2-PB9-Pad124)") (class "Default")
      (node (ref "U2") (pin "124") (pinfunction "PB9_124") (pintype "passive+no_connect"))
    )
    (net (code "75") (name "unconnected-(U2-PB11-Pad65)") (class "Default")
      (node (ref "U2") (pin "65") (pinfunction "PB11_65") (pintype "passive+no_connect"))
    )
    (net (code "76") (name "unconnected-(U2-PB12-Pad66)") (class "Default")
      (node (ref "U2") (pin "66") (pinfunction "PB12_66") (pintype "passive+no_connect"))
    )
    (net (code "77") (name "unconnected-(U2-PB13-Pad67)") (class "Default")
      (node (ref "U2") (pin "67") (pinfunction "PB13_67") (pintype "passive+no_connect"))
    )
    (net (code "78") (name "unconnected-(U2-PB15-Pad69)") (class "Default")
      (node (ref "U2") (pin "69") (pinfunction "PB15_69") (pintype "passive+no_connect"))
    )
    (net (code "79") (name "unconnected-(U2-PC0-Pad22)") (class "Default")
      (node (ref "U2") (pin "22") (pinfunction "PC0_22") (pintype "passive+no_connect"))
    )
    (net (code "80") (name "unconnected-(U2-PC1-Pad23)") (class "Default")
      (node (ref "U2") (pin "23") (pinfunction "PC1_23") (pintype "passive+no_connect"))
    )
    (net (code "81") (name "unconnected-(U2-PC2-Pad24)") (class "Default")
      (node (ref "U2") (pin "24") (pinfunction "PC2_24") (pintype "passive+no_connect"))
    )
    (net (code "82") (name "unconnected-(U2-PC3-Pad25)") (class "Default")
      (node (ref "U2") (pin "25") (pinfunction "PC3_25") (pintype "passive+no_connect"))
    )
    (net (code "83") (name "unconnected-(U2-PC5-Pad38)") (class "Default")
      (node (ref "U2") (pin "38") (pinfunction "PC5_38") (pintype "passive+no_connect"))
    )
    (net (code "84") (name "unconnected-(U2-PC6-Pad80)") (class "Default")
      (node (ref "U2") (pin "80") (pinfunction "PC6_80") (pintype "passive+no_connect"))
    )
    (net (code "85") (name "unconnected-(U2-PC7-Pad81)") (class "Default")
      (node (ref "U2") (pin "81") (pinfunction "PC7_81") (pintype "passive+no_connect"))
    )
    (net (code "86") (name "unconnected-(U2-PC8-Pad87)") (class "Default")
      (node (ref "U2") (pin "87") (pinfunction "PC8_87") (pintype "passive+no_connect"))
    )
    (net (code "87") (name "unconnected-(U2-PC13-Pad7)") (class "Default")
      (node (ref "U2") (pin "7") (pinfunction "PC13_7") (pintype "passive+no_connect"))
    )
    (net (code "88") (name "unconnected-(U2-PD2-Pad112)") (class "Default")
      (node (ref "U2") (pin "112") (pinfunction "PD2_112") (pintype "passive+no_connect"))
    )
    (net (code "89") (name "unconnected-(U2-PD3-Pad113)") (class "Default")
      (node (ref "U2") (pin "113") (pinfunction "PD3_113") (pintype "passive+no_connect"))
    )
    (net (code "90") (name "unconnected-(U2-PD4-Pad114)") (class "Default")
      (node (ref "U2") (pin "114") (pinfunction "PD4_114") (pintype "passive+no_connect"))
    )
    (net (code "91") (name "unconnected-(U2-PD5-Pad115)") (class "Default")
      (node (ref "U2") (pin "115") (pinfunction "PD5_115") (pintype "passive+no_connect"))
    )
    (net (code "92") (name "unconnected-(U2-PD6-Pad116)") (class "Default")
      (node (ref "U2") (pin "116") (pinfunction "PD6_116") (pintype "passive+no_connect"))
    )
    (net (code "93") (name "unconnected-(U2-PD7-Pad117)") (class "Default")
      (node (ref "U2") (pin "117") (pinfunction "PD7_117") (pintype "passive+no_connect"))
    )
    (net (code "94") (name "unconnected-(U2-PD9-Pad71)") (class "Default")
      (node (ref "U2") (pin "71") (pinfunction "PD9_71") (pintype "passive+no_connect"))
    )
    (net (code "95") (name "unconnected-(U2-PD11-Pad73)") (class "Default")
      (node (ref "U2") (pin "73") (pinfunction "PD11_73") (pintype "passive+no_connect"))
    )
    (net (code "96") (name "unconnected-(U2-PD13-Pad75)") (class "Default")
      (node (ref "U2") (pin "75") (pinfunction "PD13_75") (pintype "passive+no_connect"))
    )
    (net (code "97") (name "unconnected-(U2-PD14-Pad76)") (class "Default")
      (node (ref "U2") (pin "76") (pinfunction "PD14_76") (pintype "passive+no_connect"))
    )
    (net (code "98") (name "unconnected-(U2-PD15-Pad77)") (class "Default")
      (node (ref "U2") (pin "77") (pinfunction "PD15_77") (pintype "passive+no_connect"))
    )
    (net (code "99") (name "unconnected-(U2-PE0-Pad125)") (class "Default")
      (node (ref "U2") (pin "125") (pinfunction "PE0_125") (pintype "passive+no_connect"))
    )
    (net (code "100") (name "unconnected-(U2-PE1-Pad126)") (class "Default")
      (node (ref "U2") (pin "126") (pinfunction "PE1_126") (pintype "passive+no_connect"))
    )
    (net (code "101") (name "unconnected-(U2-PE2-Pad1)") (class "Default")
      (node (ref "U2") (pin "1") (pinfunction "PE2_1") (pintype "passive+no_connect"))
    )
    (net (code "102") (name "unconnected-(U2-PE3-Pad2)") (class "Default")
      (node (ref "U2") (pin "2") (pinfunction "PE3_2") (pintype "passive+no_connect"))
    )
    (net (code "103") (name "unconnected-(U2-PE4-Pad3)") (class "Default")
      (node (ref "U2") (pin "3") (pinfunction "PE4_3") (pintype "passive+no_connect"))
    )
    (net (code "104") (name "unconnected-(U2-PE5-Pad4)") (class "Default")
      (node (ref "U2") (pin "4") (pinfunction "PE5_4") (pintype "passive+no_connect"))
    )
    (net (code "105") (name "unconnected-(U2-PE6-Pad5)") (class "Default")
      (node (ref "U2") (pin "5") (pinfunction "PE6_5") (pintype "passive+no_connect"))
    )
    (net (code "106") (name "unconnected-(U2-PE7-Pad53)") (class "Default")
      (node (ref "U2") (pin "53") (pinfunction "PE7_53") (pintype "passive+no_connect"))
    )
    (net (code "107") (name "unconnected-(U2-PE8-Pad54)") (class "Default")
      (node (ref "U2") (pin "54") (pinfunction "PE8_54") (pintype "passive+no_connect"))
    )
    (net (code "108") (name "unconnected-(U2-PE9-Pad55)") (class "Default")
      (node (ref "U2") (pin "55") (pinfunction "PE9_55") (pintype "passive+no_connect"))
    )
    (net (code "109") (name "unconnected-(U2-PE10-Pad56)") (class "Default")
      (node (ref "U2") (pin "56") (pinfunction "PE10_56") (pintype "passive+no_connect"))
    )
    (net (code "110") (name "unconnected-(U2-PE11-Pad57)") (class "Default")
      (node (ref "U2") (pin "57") (pinfunction "PE11_57") (pintype "passive+no_connect"))
    )
    (net (code "111") (name "unconnected-(U2-PE12-Pad58)") (class "Default")
      (node (ref "U2") (pin "58") (pinfunction "PE12_58") (pintype "passive+no_connect"))
    )
    (net (code "112") (name "unconnected-(U2-PE13-Pad59)") (class "Default")
      (node (ref "U2") (pin "59") (pinfunction "PE13_59") (pintype "passive+no_connect"))
    )
    (net (code "113") (name "unconnected-(U2-PE14-Pad60)") (class "Default")
      (node (ref "U2") (pin "60") (pinfunction "PE14_60") (pintype "passive+no_connect"))
    )
    (net (code "114") (name "unconnected-(U2-PF2-Pad26)") (class "Default")
      (node (ref "U2") (pin "26") (pinfunction "PF2_26") (pintype "passive+no_connect"))
    )
    (net (code "115") (name "unconnected-(U2-PF3-Pad10)") (class "Default")
      (node (ref "U2") (pin "10") (pinfunction "PF3_10") (pintype "passive+no_connect"))
    )
    (net (code "116") (name "unconnected-(U2-PF4-Pad11)") (class "Default")
      (node (ref "U2") (pin "11") (pinfunction "PF4_11") (pintype "passive+no_connect"))
    )
    (net (code "117") (name "unconnected-(U2-PF5-Pad14)") (class "Default")
      (node (ref "U2") (pin "14") (pinfunction "PF5_14") (pintype "passive+no_connect"))
    )
    (net (code "118") (name "unconnected-(U2-PF6-Pad97)") (class "Default")
      (node (ref "U2") (pin "97") (pinfunction "PF6_97") (pintype "passive+no_connect"))
    )
    (net (code "119") (name "unconnected-(U2-PF7-Pad15)") (class "Default")
      (node (ref "U2") (pin "15") (pinfunction "PF7_15") (pintype "passive+no_connect"))
    )
    (net (code "120") (name "unconnected-(U2-PF8-Pad16)") (class "Default")
      (node (ref "U2") (pin "16") (pinfunction "PF8_16") (pintype "passive+no_connect"))
    )
    (net (code "121") (name "unconnected-(U2-PF9-Pad17)") (class "Default")
      (node (ref "U2") (pin "17") (pinfunction "PF9_17") (pintype "passive+no_connect"))
    )
    (net (code "122") (name "unconnected-(U2-PF10-Pad18)") (class "Default")
      (node (ref "U2") (pin "18") (pinfunction "PF10_18") (pintype "passive+no_connect"))
    )
    (net (code "123") (name "unconnected-(U2-PF11-Pad48)") (class "Default")
      (node (ref "U2") (pin "48") (pinfunction "PF11_48") (pintype "passive+no_connect"))
    )
    (net (code "124") (name "unconnected-(U2-PF12-Pad49)") (class "Default")
      (node (ref "U2") (pin "49") (pinfunction "PF12_49") (pintype "passive+no_connect"))
    )
    (net (code "125") (name "unconnected-(U2-PF13-Pad50)") (class "Default")
      (node (ref "U2") (pin "50") (pinfunction "PF13_50") (pintype "passive+no_connect"))
    )
    (net (code "126") (name "unconnected-(U2-PG0-Pad82)") (class "Default")
      (node (ref "U2") (pin "82") (pinfunction "PG0_82") (pintype "passive+no_connect"))
    )
    (net (code "127") (name "unconnected-(U2-PG2-Pad84)") (class "Default")
      (node (ref "U2") (pin "84") (pinfunction "PG2_84") (pintype "passive+no_connect"))
    )
    (net (code "128") (name "unconnected-(U2-PG4-Pad86)") (class "Default")
      (node (ref "U2") (pin "86") (pinfunction "PG4_86") (pintype "passive+no_connect"))
    )
    (net (code "129") (name "unconnected-(U2-PG6-Pad104)") (class "Default")
      (node (ref "U2") (pin "104") (pinfunction "PG6_104") (pintype "passive+no_connect"))
    )
    (net (code "130") (name "unconnected-(U2-PG7-Pad105)") (class "Default")
      (node (ref "U2") (pin "105") (pinfunction "PG7_105") (pintype "passive+no_connect"))
    )
  )
)
